# multi_sense32.net
KiCad netlist of a schematic drawn in EAGLE
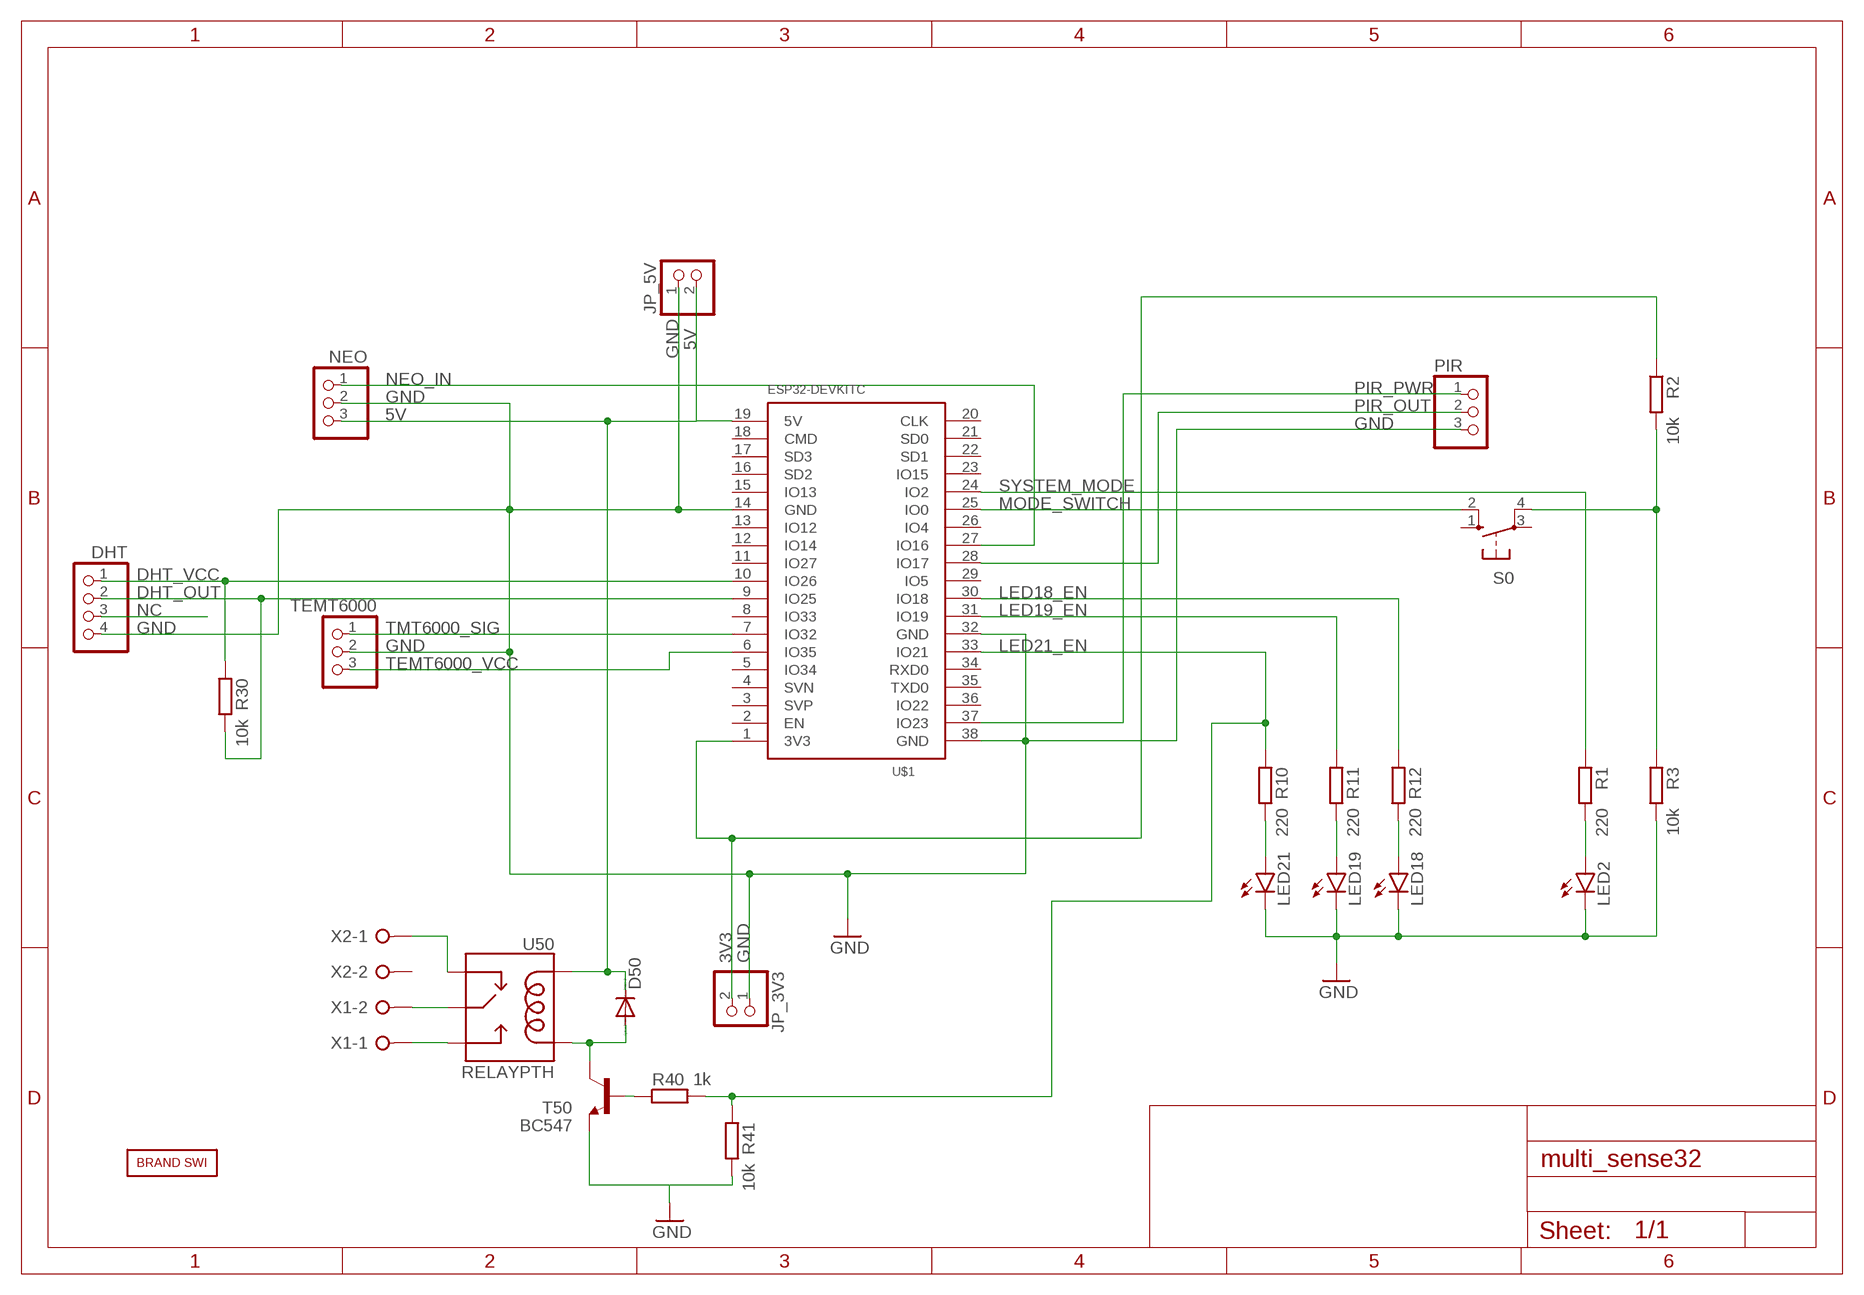
[diagram p0: schematic, sheet 1]

(export (version "E")
  (design (tool "Eeschema 10.0.6"))
  (components
    (comp (ref "D50")
      (value "1N4148DO35-7")
      (footprint "eagle-import:DO35-7")
      (libsource (lib "eagle-import") (part "1N4148DO35-7"))
    )
    (comp (ref "DHT")
      (value "PINHD-1X4")
      (footprint "eagle-import:1X04")
      (libsource (lib "eagle-import") (part "PINHD-1X4"))
    )
    (comp (ref "JP_3V3")
      (value "PINHD-1X2")
      (footprint "eagle-import:1X02")
      (libsource (lib "eagle-import") (part "PINHD-1X2"))
    )
    (comp (ref "JP_5V")
      (value "PINHD-1X2")
      (footprint "eagle-import:1X02")
      (libsource (lib "eagle-import") (part "PINHD-1X2"))
    )
    (comp (ref "LED2")
      (value "LED3MM")
      (footprint "eagle-import:LED3MM")
      (libsource (lib "eagle-import") (part "LED3MM"))
    )
    (comp (ref "LED18")
      (value "LED3MM")
      (footprint "eagle-import:LED3MM")
      (libsource (lib "eagle-import") (part "LED3MM"))
    )
    (comp (ref "LED19")
      (value "LED3MM")
      (footprint "eagle-import:LED3MM")
      (libsource (lib "eagle-import") (part "LED3MM"))
    )
    (comp (ref "LED21")
      (value "LED3MM")
      (footprint "eagle-import:LED3MM")
      (libsource (lib "eagle-import") (part "LED3MM"))
    )
    (comp (ref "NEO")
      (value "PINHD-1X3")
      (footprint "eagle-import:1X03")
      (libsource (lib "eagle-import") (part "PINHD-1X3"))
    )
    (comp (ref "PIR")
      (value "PINHD-1X3")
      (footprint "eagle-import:1X03")
      (libsource (lib "eagle-import") (part "PINHD-1X3"))
    )
    (comp (ref "R1")
      (value "220")
      (footprint "eagle-import:0207_10")
      (libsource (lib "eagle-import") (part "R-EU_0207/10"))
    )
    (comp (ref "R2")
      (value "10k")
      (footprint "eagle-import:0207_10")
      (libsource (lib "eagle-import") (part "R-EU_0207/10"))
    )
    (comp (ref "R3")
      (value "10k")
      (footprint "eagle-import:0207_10")
      (libsource (lib "eagle-import") (part "R-EU_0207/10"))
    )
    (comp (ref "R10")
      (value "220")
      (footprint "eagle-import:0207_10")
      (libsource (lib "eagle-import") (part "R-EU_0207/10"))
    )
    (comp (ref "R11")
      (value "220")
      (footprint "eagle-import:0207_10")
      (libsource (lib "eagle-import") (part "R-EU_0207/10"))
    )
    (comp (ref "R12")
      (value "220")
      (footprint "eagle-import:0207_10")
      (libsource (lib "eagle-import") (part "R-EU_0207/10"))
    )
    (comp (ref "R30")
      (value "10k")
      (footprint "eagle-import:0207_10")
      (libsource (lib "eagle-import") (part "R-EU_0207/10"))
    )
    (comp (ref "R40")
      (value "1k")
      (footprint "eagle-import:0207_10")
      (libsource (lib "eagle-import") (part "R-EU_0207/10"))
    )
    (comp (ref "R41")
      (value "10k")
      (footprint "eagle-import:0207_10")
      (libsource (lib "eagle-import") (part "R-EU_0207/10"))
    )
    (comp (ref "S0")
      (value "10-XX")
      (footprint "eagle-import:B3F-10XX")
      (fields (field (name "MPN") "B3F-1000"))
      (libsource (lib "eagle-import") (part "10-XX"))
    )
    (comp (ref "T50")
      (value "BC547")
      (footprint "eagle-import:TO92")
      (libsource (lib "eagle-import") (part "BC547"))
    )
    (comp (ref "TEMT6000")
      (value "PINHD-1X3")
      (footprint "eagle-import:1X03")
      (libsource (lib "eagle-import") (part "PINHD-1X3"))
    )
    (comp (ref "U$1")
      (value "ESP32DEVKITC")
      (footprint "eagle-import:ESP32-DEVKITC")
      (libsource (lib "eagle-import") (part "ESP32DEVKITC"))
    )
    (comp (ref "U$2")
      (value "BRAND_SWI5X7")
      (footprint "eagle-import:BRAND_SWI_5X7")
      (libsource (lib "eagle-import") (part "BRAND_SWI5X7"))
    )
    (comp (ref "U50")
      (value "RELAYPTH")
      (footprint "eagle-import:SRD-05VDC-SL-C")
      (libsource (lib "eagle-import") (part "RELAYPTH"))
    )
    (comp (ref "X1")
      (value "W237-02P")
      (footprint "eagle-import:W237-132")
      (libsource (lib "eagle-import") (part "W237-02P"))
    )
    (comp (ref "X2")
      (value "W237-02P")
      (footprint "eagle-import:W237-132")
      (libsource (lib "eagle-import") (part "W237-02P"))
    )
  )
  (nets
    (net (code "1") (name "/3V3") (class "Default")
      (node (ref "JP_3V3") (pin "2") (pinfunction "2_2") (pintype "passive"))
      (node (ref "R2") (pin "1") (pinfunction "1_1") (pintype "passive"))
      (node (ref "U$1") (pin "1") (pinfunction "3V3_1") (pintype "bidirectional"))
    )
    (net (code "2") (name "/5V") (class "Default")
      (node (ref "D50") (pin "C") (pinfunction "C_C") (pintype "passive"))
      (node (ref "JP_5V") (pin "2") (pinfunction "2_2") (pintype "passive"))
      (node (ref "NEO") (pin "3") (pinfunction "3_3") (pintype "passive"))
      (node (ref "U$1") (pin "19") (pinfunction "5V_19") (pintype "bidirectional"))
      (node (ref "U50") (pin "COIL1") (pinfunction "COIL1_COIL1") (pintype "bidirectional"))
    )
    (net (code "3") (name "/DHT_OUT") (class "Default")
      (node (ref "DHT") (pin "2") (pinfunction "2_2") (pintype "passive"))
      (node (ref "R30") (pin "2") (pinfunction "2_2") (pintype "passive"))
      (node (ref "U$1") (pin "9") (pinfunction "IO25_9") (pintype "bidirectional"))
    )
    (net (code "4") (name "/DHT_VCC") (class "Default")
      (node (ref "DHT") (pin "1") (pinfunction "1_1") (pintype "passive"))
      (node (ref "R30") (pin "1") (pinfunction "1_1") (pintype "passive"))
      (node (ref "U$1") (pin "10") (pinfunction "IO26_10") (pintype "bidirectional"))
    )
    (net (code "5") (name "/LED18_EN") (class "Default")
      (node (ref "R12") (pin "1") (pinfunction "1_1") (pintype "passive"))
      (node (ref "U$1") (pin "30") (pinfunction "IO18_30") (pintype "bidirectional"))
    )
    (net (code "6") (name "/LED19_EN") (class "Default")
      (node (ref "R11") (pin "1") (pinfunction "1_1") (pintype "passive"))
      (node (ref "U$1") (pin "31") (pinfunction "IO19_31") (pintype "bidirectional"))
    )
    (net (code "7") (name "/LED21_EN") (class "Default")
      (node (ref "R10") (pin "1") (pinfunction "1_1") (pintype "passive"))
      (node (ref "R40") (pin "2") (pinfunction "2_2") (pintype "passive"))
      (node (ref "R41") (pin "1") (pinfunction "1_1") (pintype "passive"))
      (node (ref "U$1") (pin "33") (pinfunction "IO21_33") (pintype "bidirectional"))
    )
    (net (code "8") (name "/MODE_SWITCH") (class "Default")
      (node (ref "S0") (pin "2") (pinfunction "S1_2") (pintype "passive"))
      (node (ref "U$1") (pin "25") (pinfunction "IO0_25") (pintype "bidirectional"))
    )
    (net (code "9") (name "/NC") (class "Default")
      (node (ref "DHT") (pin "3") (pinfunction "3_3") (pintype "passive"))
    )
    (net (code "10") (name "/NEO_IN") (class "Default")
      (node (ref "NEO") (pin "1") (pinfunction "1_1") (pintype "passive"))
      (node (ref "U$1") (pin "27") (pinfunction "IO16_27") (pintype "bidirectional"))
    )
    (net (code "11") (name "/PIR_OUT") (class "Default")
      (node (ref "PIR") (pin "2") (pinfunction "2_2") (pintype "passive"))
      (node (ref "U$1") (pin "28") (pinfunction "IO17_28") (pintype "bidirectional"))
    )
    (net (code "12") (name "/PIR_PWR") (class "Default")
      (node (ref "PIR") (pin "1") (pinfunction "1_1") (pintype "passive"))
      (node (ref "U$1") (pin "37") (pinfunction "IO23_37") (pintype "bidirectional"))
    )
    (net (code "13") (name "/SYSTEM_MODE") (class "Default")
      (node (ref "R1") (pin "1") (pinfunction "1_1") (pintype "passive"))
      (node (ref "U$1") (pin "24") (pinfunction "IO2_24") (pintype "bidirectional"))
    )
    (net (code "14") (name "/TEMT6000_VCC") (class "Default")
      (node (ref "TEMT6000") (pin "3") (pinfunction "3_3") (pintype "passive"))
      (node (ref "U$1") (pin "6") (pinfunction "IO35_6") (pintype "bidirectional"))
    )
    (net (code "15") (name "/TMT6000_SIG") (class "Default")
      (node (ref "TEMT6000") (pin "1") (pinfunction "1_1") (pintype "passive"))
      (node (ref "U$1") (pin "7") (pinfunction "IO32_7") (pintype "bidirectional"))
    )
    (net (code "16") (name "GND") (class "Default")
      (node (ref "DHT") (pin "4") (pinfunction "4_4") (pintype "passive"))
      (node (ref "JP_3V3") (pin "1") (pinfunction "1_1") (pintype "passive"))
      (node (ref "JP_5V") (pin "1") (pinfunction "1_1") (pintype "passive"))
      (node (ref "LED18") (pin "K") (pinfunction "C_K") (pintype "passive"))
      (node (ref "LED19") (pin "K") (pinfunction "C_K") (pintype "passive"))
      (node (ref "LED2") (pin "K") (pinfunction "C_K") (pintype "passive"))
      (node (ref "LED21") (pin "K") (pinfunction "C_K") (pintype "passive"))
      (node (ref "NEO") (pin "2") (pinfunction "2_2") (pintype "passive"))
      (node (ref "PIR") (pin "3") (pinfunction "3_3") (pintype "passive"))
      (node (ref "R3") (pin "2") (pinfunction "2_2") (pintype "passive"))
      (node (ref "R41") (pin "2") (pinfunction "2_2") (pintype "passive"))
      (node (ref "T50") (pin "1") (pinfunction "E_1") (pintype "passive"))
      (node (ref "TEMT6000") (pin "2") (pinfunction "2_2") (pintype "passive"))
      (node (ref "U$1") (pin "14") (pinfunction "GND_14") (pintype "bidirectional"))
      (node (ref "U$1") (pin "32") (pinfunction "GND_32") (pintype "bidirectional"))
      (node (ref "U$1") (pin "38") (pinfunction "GND_38") (pintype "bidirectional"))
    )
    (net (code "17") (name "Net-(LED2-PadA)") (class "Default")
      (node (ref "LED2") (pin "A") (pinfunction "A_A") (pintype "passive"))
      (node (ref "R1") (pin "2") (pinfunction "2_2") (pintype "passive"))
    )
    (net (code "18") (name "Net-(LED18-PadA)") (class "Default")
      (node (ref "LED18") (pin "A") (pinfunction "A_A") (pintype "passive"))
      (node (ref "R12") (pin "2") (pinfunction "2_2") (pintype "passive"))
    )
    (net (code "19") (name "Net-(LED19-PadA)") (class "Default")
      (node (ref "LED19") (pin "A") (pinfunction "A_A") (pintype "passive"))
      (node (ref "R11") (pin "2") (pinfunction "2_2") (pintype "passive"))
    )
    (net (code "20") (name "Net-(LED21-PadA)") (class "Default")
      (node (ref "LED21") (pin "A") (pinfunction "A_A") (pintype "passive"))
      (node (ref "R10") (pin "2") (pinfunction "2_2") (pintype "passive"))
    )
    (net (code "21") (name "Net-(S0-P1)") (class "Default")
      (node (ref "R2") (pin "2") (pinfunction "2_2") (pintype "passive"))
      (node (ref "R3") (pin "1") (pinfunction "1_1") (pintype "passive"))
      (node (ref "S0") (pin "4") (pinfunction "P1_4") (pintype "passive"))
    )
    (net (code "22") (name "Net-(T50-B)") (class "Default")
      (node (ref "R40") (pin "1") (pinfunction "1_1") (pintype "passive"))
      (node (ref "T50") (pin "2") (pinfunction "B_2") (pintype "passive"))
    )
    (net (code "23") (name "Net-(T50-C)") (class "Default")
      (node (ref "D50") (pin "A") (pinfunction "A_A") (pintype "passive"))
      (node (ref "T50") (pin "3") (pinfunction "C_3") (pintype "passive"))
      (node (ref "U50") (pin "COIL0") (pinfunction "COIL0_COIL0") (pintype "bidirectional"))
    )
    (net (code "24") (name "Net-(U50-SWCLOSE)") (class "Default")
      (node (ref "U50") (pin "SWCLOSED") (pinfunction "SWCLOSE_SWCLOSED") (pintype "bidirectional"))
      (node (ref "X2") (pin "1") (pinfunction "KL_1") (pintype "passive"))
    )
    (net (code "25") (name "Net-(X1A-KL)") (class "Default")
      (node (ref "U50") (pin "SWOPEN") (pinfunction "SWOPEN_SWOPEN") (pintype "bidirectional"))
      (node (ref "X1") (pin "1") (pinfunction "KL_1") (pintype "passive"))
    )
    (net (code "26") (name "Net-(X1B-KL)") (class "Default")
      (node (ref "U50") (pin "SWCOMMON") (pinfunction "SWCOMMON_SWCOMMON") (pintype "bidirectional"))
      (node (ref "X1") (pin "2") (pinfunction "KL_2") (pintype "passive"))
    )
    (net (code "27") (name "unconnected-(S0-P-Pad3)") (class "Default")
      (node (ref "S0") (pin "3") (pinfunction "P_3") (pintype "passive"))
    )
    (net (code "28") (name "unconnected-(S0-S-Pad1)") (class "Default")
      (node (ref "S0") (pin "1") (pinfunction "S_1") (pintype "passive"))
    )
    (net (code "29") (name "unconnected-(U$1-CLK-Pad20)") (class "Default")
      (node (ref "U$1") (pin "20") (pinfunction "CLK_20") (pintype "bidirectional"))
    )
    (net (code "30") (name "unconnected-(U$1-CMD-Pad18)") (class "Default")
      (node (ref "U$1") (pin "18") (pinfunction "CMD_18") (pintype "bidirectional"))
    )
    (net (code "31") (name "unconnected-(U$1-EN-Pad2)") (class "Default")
      (node (ref "U$1") (pin "2") (pinfunction "EN_2") (pintype "bidirectional"))
    )
    (net (code "32") (name "unconnected-(U$1-IO4-Pad26)") (class "Default")
      (node (ref "U$1") (pin "26") (pinfunction "IO4_26") (pintype "bidirectional"))
    )
    (net (code "33") (name "unconnected-(U$1-IO5-Pad29)") (class "Default")
      (node (ref "U$1") (pin "29") (pinfunction "IO5_29") (pintype "bidirectional"))
    )
    (net (code "34") (name "unconnected-(U$1-IO12-Pad13)") (class "Default")
      (node (ref "U$1") (pin "13") (pinfunction "IO12_13") (pintype "bidirectional"))
    )
    (net (code "35") (name "unconnected-(U$1-IO13-Pad15)") (class "Default")
      (node (ref "U$1") (pin "15") (pinfunction "IO13_15") (pintype "bidirectional"))
    )
    (net (code "36") (name "unconnected-(U$1-IO14-Pad12)") (class "Default")
      (node (ref "U$1") (pin "12") (pinfunction "IO14_12") (pintype "bidirectional"))
    )
    (net (code "37") (name "unconnected-(U$1-IO15-Pad23)") (class "Default")
      (node (ref "U$1") (pin "23") (pinfunction "IO15_23") (pintype "bidirectional"))
    )
    (net (code "38") (name "unconnected-(U$1-IO22-Pad36)") (class "Default")
      (node (ref "U$1") (pin "36") (pinfunction "IO22_36") (pintype "bidirectional"))
    )
    (net (code "39") (name "unconnected-(U$1-IO27-Pad11)") (class "Default")
      (node (ref "U$1") (pin "11") (pinfunction "IO27_11") (pintype "bidirectional"))
    )
    (net (code "40") (name "unconnected-(U$1-IO33-Pad8)") (class "Default")
      (node (ref "U$1") (pin "8") (pinfunction "IO33_8") (pintype "bidirectional"))
    )
    (net (code "41") (name "unconnected-(U$1-IO34-Pad5)") (class "Default")
      (node (ref "U$1") (pin "5") (pinfunction "IO34_5") (pintype "bidirectional"))
    )
    (net (code "42") (name "unconnected-(U$1-RXD0-Pad34)") (class "Default")
      (node (ref "U$1") (pin "34") (pinfunction "RXD0_34") (pintype "bidirectional"))
    )
    (net (code "43") (name "unconnected-(U$1-SD0-Pad21)") (class "Default")
      (node (ref "U$1") (pin "21") (pinfunction "SD0_21") (pintype "bidirectional"))
    )
    (net (code "44") (name "unconnected-(U$1-SD1-Pad22)") (class "Default")
      (node (ref "U$1") (pin "22") (pinfunction "SD1_22") (pintype "bidirectional"))
    )
    (net (code "45") (name "unconnected-(U$1-SD2-Pad16)") (class "Default")
      (node (ref "U$1") (pin "16") (pinfunction "SD2_16") (pintype "bidirectional"))
    )
    (net (code "46") (name "unconnected-(U$1-SD3-Pad17)") (class "Default")
      (node (ref "U$1") (pin "17") (pinfunction "SD3_17") (pintype "bidirectional"))
    )
    (net (code "47") (name "unconnected-(U$1-SVN-Pad4)") (class "Default")
      (node (ref "U$1") (pin "4") (pinfunction "SVN_4") (pintype "bidirectional"))
    )
    (net (code "48") (name "unconnected-(U$1-SVP-Pad3)") (class "Default")
      (node (ref "U$1") (pin "3") (pinfunction "SVP_3") (pintype "bidirectional"))
    )
    (net (code "49") (name "unconnected-(U$1-TXD0-Pad35)") (class "Default")
      (node (ref "U$1") (pin "35") (pinfunction "TXD0_35") (pintype "bidirectional"))
    )
    (net (code "50") (name "unconnected-(X2B-KL-Pad2)") (class "Default")
      (node (ref "X2") (pin "2") (pinfunction "KL_2") (pintype "passive"))
    )
  )
)
